# thermocouple.net
KiCad netlist of a schematic drawn in Altium Designer
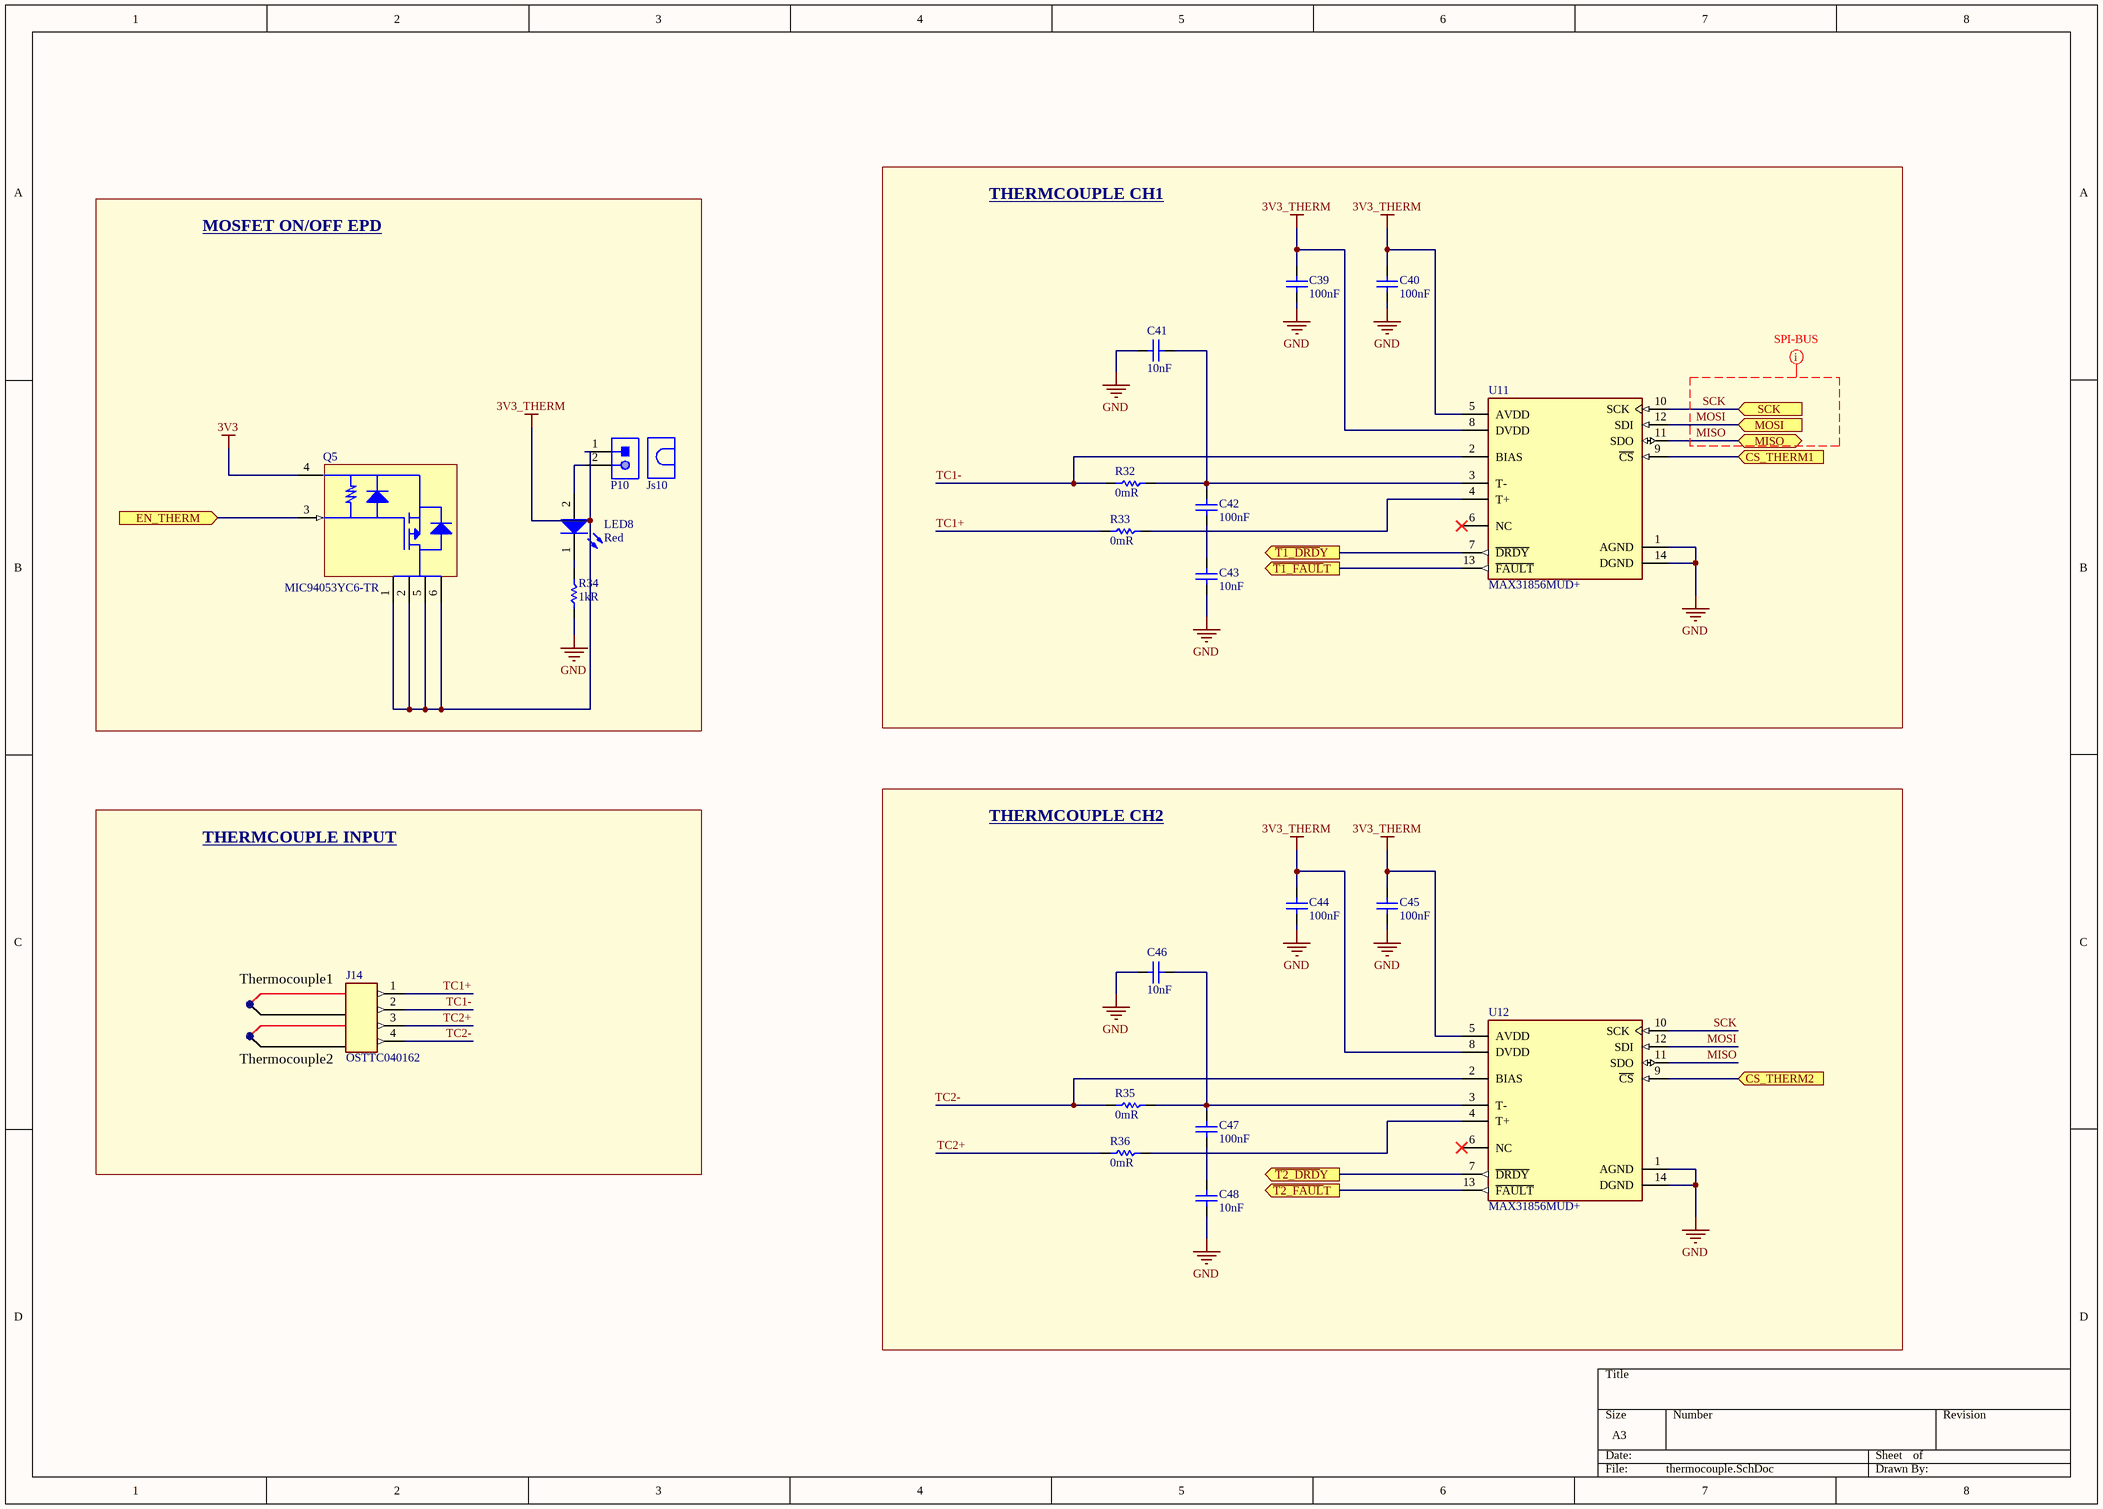
[diagram p0: thermocouple.SchDoc]

(export (version "E")
  (design (tool "Eeschema 10.0.6"))
  (components
    (comp (ref "C39")
      (value "100nF")
      (footprint "Cap 0805 (2012 Metric)")
      (fields
        (field (name "MANUFACTURER") "Yageo")
        (field (name "MANUFACTURER PART NUMBER") "CC0805ZRY5V9BB104")
        (field (name "TOLERANCE") "80%")
      )
      (libsource (lib "Daniel_Integrated_Library") (part "Capacitor"))
    )
    (comp (ref "C40")
      (value "100nF")
      (footprint "Cap 0805 (2012 Metric)")
      (fields
        (field (name "MANUFACTURER") "Yageo")
        (field (name "MANUFACTURER PART NUMBER") "CC0805ZRY5V9BB104")
        (field (name "TOLERANCE") "80%")
      )
      (libsource (lib "Daniel_Integrated_Library") (part "Capacitor"))
    )
    (comp (ref "C41")
      (value "10nF")
      (footprint "Cap 0603 (1608 Metric)")
      (description "Cap Ceramic 0.01uF 50V X7R 10% SMD 0603 125C Automotive T/R")
      (fields
        (field (name "MANUFACTURER") "Yageo")
        (field (name "MANUFACTURER PART NUMBER") "CC0603KRX7R9BB103")
      )
      (libsource (lib "Daniel_Integrated_Library") (part "Capacitor"))
    )
    (comp (ref "C42")
      (value "100nF")
      (footprint "Cap 0805 (2012 Metric)")
      (fields
        (field (name "MANUFACTURER") "Yageo")
        (field (name "MANUFACTURER PART NUMBER") "CC0805ZRY5V9BB104")
        (field (name "TOLERANCE") "80%")
      )
      (libsource (lib "Daniel_Integrated_Library") (part "Capacitor"))
    )
    (comp (ref "C43")
      (value "10nF")
      (footprint "Cap 0603 (1608 Metric)")
      (description "Cap Ceramic 0.01uF 50V X7R 10% SMD 0603 125C Automotive T/R")
      (fields
        (field (name "MANUFACTURER") "Yageo")
        (field (name "MANUFACTURER PART NUMBER") "CC0603KRX7R9BB103")
      )
      (libsource (lib "Daniel_Integrated_Library") (part "Capacitor"))
    )
    (comp (ref "C44")
      (value "100nF")
      (footprint "Cap 0805 (2012 Metric)")
      (fields
        (field (name "MANUFACTURER") "Yageo")
        (field (name "MANUFACTURER PART NUMBER") "CC0805ZRY5V9BB104")
        (field (name "TOLERANCE") "80%")
      )
      (libsource (lib "Daniel_Integrated_Library") (part "Capacitor"))
    )
    (comp (ref "C45")
      (value "100nF")
      (footprint "Cap 0805 (2012 Metric)")
      (fields
        (field (name "MANUFACTURER") "Yageo")
        (field (name "MANUFACTURER PART NUMBER") "CC0805ZRY5V9BB104")
        (field (name "TOLERANCE") "80%")
      )
      (libsource (lib "Daniel_Integrated_Library") (part "Capacitor"))
    )
    (comp (ref "C46")
      (value "10nF")
      (footprint "Cap 0603 (1608 Metric)")
      (description "Cap Ceramic 0.01uF 50V X7R 10% SMD 0603 125C Automotive T/R")
      (fields
        (field (name "MANUFACTURER") "Yageo")
        (field (name "MANUFACTURER PART NUMBER") "CC0603KRX7R9BB103")
      )
      (libsource (lib "Daniel_Integrated_Library") (part "Capacitor"))
    )
    (comp (ref "C47")
      (value "100nF")
      (footprint "Cap 0805 (2012 Metric)")
      (fields
        (field (name "MANUFACTURER") "Yageo")
        (field (name "MANUFACTURER PART NUMBER") "CC0805ZRY5V9BB104")
        (field (name "TOLERANCE") "80%")
      )
      (libsource (lib "Daniel_Integrated_Library") (part "Capacitor"))
    )
    (comp (ref "C48")
      (value "10nF")
      (footprint "Cap 0603 (1608 Metric)")
      (description "Cap Ceramic 0.01uF 50V X7R 10% SMD 0603 125C Automotive T/R")
      (fields
        (field (name "MANUFACTURER") "Yageo")
        (field (name "MANUFACTURER PART NUMBER") "CC0603KRX7R9BB103")
      )
      (libsource (lib "Daniel_Integrated_Library") (part "Capacitor"))
    )
    (comp (ref "J14")
      (value "OSTTC040162")
      (footprint "OSTTC040162")
      (description "Conn Terminal Block 4 POS 5mm Solder ST Thru-Hole 15A")
      (fields (field (name "MANUFACTURER") "On-Shore Technology") (field (name "VOLTAGE") "300V"))
      (libsource (lib "stratos") (part "OSTTC040162"))
    )
    (comp (ref "Js10")
      (value "Jumper (2x1)")
      (footprint "Header JMP 2x1")
      (description "2 (1 x 2) Position Shunt Connector Black Open Top 0.100\" (2.54mm) Gold")
      (fields
        (field (name "MANUFACTURER") "Sullins")
        (field (name "MANUFACTURER PART NUMBER") "QPC02SXGN-RC")
      )
      (libsource (lib "Daniel_Integrated_Library") (part "Jumper (2x1)"))
    )
    (comp (ref "LED8")
      (value "Red")
      (footprint "LED 0805(2012 METRIC)")
      (description "SMD LED red 2.4 V 0805, 150080RS75000, Würth Elektronik")
      (fields
        (field (name "MANUFACTURER") "Wurth Electronics")
        (field (name "MANUFACTURER PART NUMBER") "150080RS75000")
      )
      (libsource (lib "Daniel_Integrated_Library") (part "LED"))
    )
    (comp (ref "P10")
      (value "Header 2x1")
      (footprint "Header 2x1")
      (description "Connector Header Through Hole 2 position 0.100\" (2.54mm)")
      (fields
        (field (name "MANUFACTURER") "Amphenol FCI")
        (field (name "MANUFACTURER PART NUMBER") "68001-402HLF")
      )
      (libsource (lib "Daniel_Integrated_Library") (part "Header 2x1"))
    )
    (comp (ref "Q5")
      (value "MIC94053YC6-TR")
      (footprint "SC-70-6")
      (description "P-Channel 6V 2A (Ta) 270mW (Ta) Surface Mount SC-70-6")
      (fields (field (name "MANUFACTURER") "Microchip"))
      (libsource (lib "Daniel_Integrated_Library") (part "TransistorMosfet(Load)"))
    )
    (comp (ref "R32")
      (value "0mR")
      (footprint "Res 0805 (2012 Metric)")
      (description "CR Series 0805 0 O Jumper Surface Mount Thick Film Chip Resistor")
      (fields
        (field (name "MANUFACTURER") "Viking Tech")
        (field (name "MANUFACTURER PART NUMBER") "CR-05JL7----0R")
      )
      (libsource (lib "Daniel_Integrated_Library") (part "Resistor"))
    )
    (comp (ref "R33")
      (value "0mR")
      (footprint "Res 0805 (2012 Metric)")
      (description "CR Series 0805 0 O Jumper Surface Mount Thick Film Chip Resistor")
      (fields
        (field (name "MANUFACTURER") "Viking Tech")
        (field (name "MANUFACTURER PART NUMBER") "CR-05JL7----0R")
      )
      (libsource (lib "Daniel_Integrated_Library") (part "Resistor"))
    )
    (comp (ref "R34")
      (value "1kR")
      (footprint "Res 0805 (2012 Metric)")
      (description "RES 1K OHM 1% 1/4W 0805")
      (fields
        (field (name "MANUFACTURER") "Stackpole Electronics")
        (field (name "MANUFACTURER PART NUMBER") "RNCP0805FTD1K00")
      )
      (libsource (lib "Daniel_Integrated_Library") (part "Resistor"))
    )
    (comp (ref "R35")
      (value "0mR")
      (footprint "Res 0805 (2012 Metric)")
      (description "CR Series 0805 0 O Jumper Surface Mount Thick Film Chip Resistor")
      (fields
        (field (name "MANUFACTURER") "Viking Tech")
        (field (name "MANUFACTURER PART NUMBER") "CR-05JL7----0R")
      )
      (libsource (lib "Daniel_Integrated_Library") (part "Resistor"))
    )
    (comp (ref "R36")
      (value "0mR")
      (footprint "Res 0805 (2012 Metric)")
      (description "CR Series 0805 0 O Jumper Surface Mount Thick Film Chip Resistor")
      (fields
        (field (name "MANUFACTURER") "Viking Tech")
        (field (name "MANUFACTURER PART NUMBER") "CR-05JL7----0R")
      )
      (libsource (lib "Daniel_Integrated_Library") (part "Resistor"))
    )
    (comp (ref "U11")
      (value "MAX31856MUD+")
      (footprint "MAX31856MUD+")
      (description "Precision Thermocouple to Digital Converter 14-Pin TSSOP Tube")
      (fields (field (name "MANUFACTURER") "Maxim"))
      (libsource (lib "stratos") (part "MAX31856MUD+"))
    )
    (comp (ref "U12")
      (value "MAX31856MUD+")
      (footprint "MAX31856MUD+")
      (description "Precision Thermocouple to Digital Converter 14-Pin TSSOP Tube")
      (fields (field (name "MANUFACTURER") "Maxim"))
      (libsource (lib "stratos") (part "MAX31856MUD+"))
    )
  )
  (nets
    (net (code "1") (name "/CS_THERM1") (class "Default")
      (node (ref "U11") (pin "9") (pinfunction "~{CS}_9") (pintype "input"))
    )
    (net (code "2") (name "/CS_THERM2") (class "Default")
      (node (ref "U12") (pin "9") (pinfunction "~{CS}_9") (pintype "input"))
    )
    (net (code "3") (name "/EN_THERM") (class "Default")
      (node (ref "Q5") (pin "3") (pinfunction "G_3") (pintype "input"))
    )
    (net (code "4") (name "/MISO") (class "Default")
      (node (ref "U11") (pin "11") (pinfunction "SDO_11") (pintype "bidirectional"))
      (node (ref "U12") (pin "11") (pinfunction "SDO_11") (pintype "bidirectional"))
    )
    (net (code "5") (name "/MOSI") (class "Default")
      (node (ref "U11") (pin "12") (pinfunction "SDI_12") (pintype "input"))
      (node (ref "U12") (pin "12") (pinfunction "SDI_12") (pintype "input"))
    )
    (net (code "6") (name "/SCK") (class "Default")
      (node (ref "U11") (pin "10") (pinfunction "SCK_10") (pintype "input"))
      (node (ref "U12") (pin "10") (pinfunction "SCK_10") (pintype "input"))
    )
    (net (code "7") (name "/TC1+") (class "Default")
      (node (ref "J14") (pin "1") (pinfunction "1_1") (pintype "output"))
      (node (ref "R33") (pin "1") (pinfunction "1_1") (pintype "passive"))
    )
    (net (code "8") (name "/TC1-") (class "Default")
      (node (ref "J14") (pin "2") (pinfunction "2_2") (pintype "output"))
      (node (ref "R32") (pin "1") (pinfunction "1_1") (pintype "passive"))
      (node (ref "U11") (pin "2") (pinfunction "BIAS_2") (pintype "passive"))
    )
    (net (code "9") (name "/TC2+") (class "Default")
      (node (ref "J14") (pin "3") (pinfunction "3_3") (pintype "output"))
      (node (ref "R36") (pin "1") (pinfunction "1_1") (pintype "passive"))
    )
    (net (code "10") (name "/TC2-") (class "Default")
      (node (ref "J14") (pin "4") (pinfunction "4_4") (pintype "output"))
      (node (ref "R35") (pin "1") (pinfunction "1_1") (pintype "passive"))
      (node (ref "U12") (pin "2") (pinfunction "BIAS_2") (pintype "passive"))
    )
    (net (code "11") (name "/~{T1_DRD}Y") (class "Default")
      (node (ref "U11") (pin "7") (pinfunction "~{DRDY}_7") (pintype "output"))
    )
    (net (code "12") (name "/~{T1_FAUL}T") (class "Default")
      (node (ref "U11") (pin "13") (pinfunction "~{FAULT}_13") (pintype "output"))
    )
    (net (code "13") (name "/~{T2_DRD}Y") (class "Default")
      (node (ref "U12") (pin "7") (pinfunction "~{DRDY}_7") (pintype "output"))
    )
    (net (code "14") (name "/~{T2_FAUL}T") (class "Default")
      (node (ref "U12") (pin "13") (pinfunction "~{FAULT}_13") (pintype "output"))
    )
    (net (code "15") (name "3V3") (class "Default")
      (node (ref "Q5") (pin "4") (pinfunction "S_4") (pintype "passive"))
    )
    (net (code "16") (name "3V3_THERM") (class "Default")
      (node (ref "C39") (pin "1") (pinfunction "1_1") (pintype "passive"))
      (node (ref "C40") (pin "1") (pinfunction "1_1") (pintype "passive"))
      (node (ref "C44") (pin "1") (pinfunction "1_1") (pintype "passive"))
      (node (ref "C45") (pin "1") (pinfunction "1_1") (pintype "passive"))
      (node (ref "P10") (pin "1") (pinfunction "1_1") (pintype "passive"))
      (node (ref "Q5") (pin "1") (pinfunction "D_1") (pintype "passive"))
      (node (ref "Q5") (pin "2") (pinfunction "D_2") (pintype "passive"))
      (node (ref "Q5") (pin "5") (pinfunction "D_5") (pintype "passive"))
      (node (ref "Q5") (pin "6") (pinfunction "D_6") (pintype "passive"))
      (node (ref "U11") (pin "5") (pinfunction "AVDD_5") (pintype "power_in"))
      (node (ref "U11") (pin "8") (pinfunction "DVDD_8") (pintype "power_in"))
      (node (ref "U12") (pin "5") (pinfunction "AVDD_5") (pintype "power_in"))
      (node (ref "U12") (pin "8") (pinfunction "DVDD_8") (pintype "power_in"))
    )
    (net (code "17") (name "GND") (class "Default")
      (node (ref "C39") (pin "2") (pinfunction "2_2") (pintype "passive"))
      (node (ref "C40") (pin "2") (pinfunction "2_2") (pintype "passive"))
      (node (ref "C41") (pin "1") (pinfunction "1_1") (pintype "passive"))
      (node (ref "C43") (pin "1") (pinfunction "1_1") (pintype "passive"))
      (node (ref "C44") (pin "2") (pinfunction "2_2") (pintype "passive"))
      (node (ref "C45") (pin "2") (pinfunction "2_2") (pintype "passive"))
      (node (ref "C46") (pin "1") (pinfunction "1_1") (pintype "passive"))
      (node (ref "C48") (pin "1") (pinfunction "1_1") (pintype "passive"))
      (node (ref "R34") (pin "2") (pinfunction "2_2") (pintype "passive"))
      (node (ref "U11") (pin "1") (pinfunction "AGND_1") (pintype "power_in"))
      (node (ref "U11") (pin "14") (pinfunction "DGND_14") (pintype "power_in"))
      (node (ref "U12") (pin "1") (pinfunction "AGND_1") (pintype "power_in"))
      (node (ref "U12") (pin "14") (pinfunction "DGND_14") (pintype "power_in"))
    )
    (net (code "18") (name "Net-(C42-Pad2)") (class "Default")
      (node (ref "C42") (pin "2") (pinfunction "2_2") (pintype "passive"))
      (node (ref "C43") (pin "2") (pinfunction "2_2") (pintype "passive"))
    )
    (net (code "19") (name "Net-(C47-Pad2)") (class "Default")
      (node (ref "C47") (pin "2") (pinfunction "2_2") (pintype "passive"))
      (node (ref "C48") (pin "2") (pinfunction "2_2") (pintype "passive"))
    )
    (net (code "20") (name "Net-(LED8-A)") (class "Default")
      (node (ref "LED8") (pin "2") (pinfunction "A_2") (pintype "passive"))
      (node (ref "P10") (pin "2") (pinfunction "2_2") (pintype "passive"))
    )
    (net (code "21") (name "Net-(LED8-K)") (class "Default")
      (node (ref "LED8") (pin "1") (pinfunction "K_1") (pintype "passive"))
      (node (ref "R34") (pin "1") (pinfunction "1_1") (pintype "passive"))
    )
    (net (code "22") (name "Net-(U11-T+)") (class "Default")
      (node (ref "R33") (pin "2") (pinfunction "2_2") (pintype "passive"))
      (node (ref "U11") (pin "4") (pinfunction "T+_4") (pintype "passive"))
    )
    (net (code "23") (name "Net-(U11-T-)") (class "Default")
      (node (ref "C41") (pin "2") (pinfunction "2_2") (pintype "passive"))
      (node (ref "C42") (pin "1") (pinfunction "1_1") (pintype "passive"))
      (node (ref "R32") (pin "2") (pinfunction "2_2") (pintype "passive"))
      (node (ref "U11") (pin "3") (pinfunction "T-_3") (pintype "passive"))
    )
    (net (code "24") (name "Net-(U12-T+)") (class "Default")
      (node (ref "R36") (pin "2") (pinfunction "2_2") (pintype "passive"))
      (node (ref "U12") (pin "4") (pinfunction "T+_4") (pintype "passive"))
    )
    (net (code "25") (name "Net-(U12-T-)") (class "Default")
      (node (ref "C46") (pin "2") (pinfunction "2_2") (pintype "passive"))
      (node (ref "C47") (pin "1") (pinfunction "1_1") (pintype "passive"))
      (node (ref "R35") (pin "2") (pinfunction "2_2") (pintype "passive"))
      (node (ref "U12") (pin "3") (pinfunction "T-_3") (pintype "passive"))
    )
    (net (code "26") (name "unconnected-(U11-NC-Pad6)") (class "Default")
      (node (ref "U11") (pin "6") (pinfunction "NC_6") (pintype "passive+no_connect"))
    )
    (net (code "27") (name "unconnected-(U12-NC-Pad6)") (class "Default")
      (node (ref "U12") (pin "6") (pinfunction "NC_6") (pintype "passive+no_connect"))
    )
  )
)
